# Break.net
KiCad netlist of a schematic drawn in EAGLE
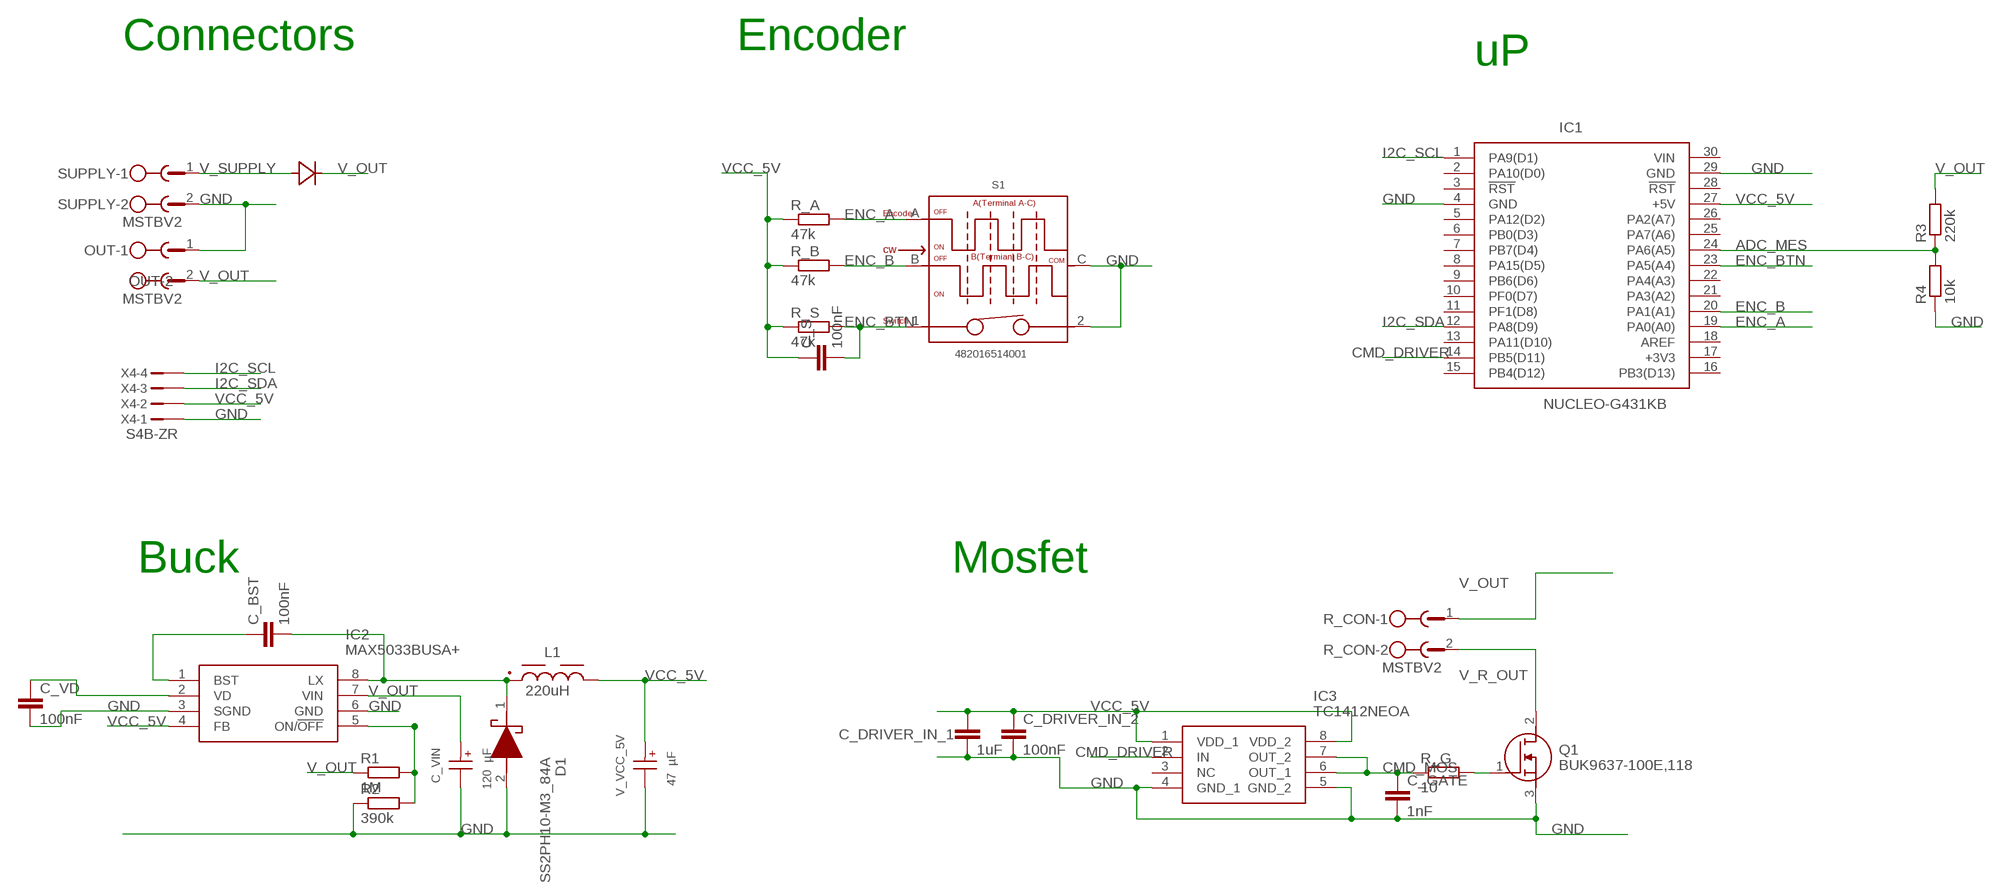
[diagram p0: schematic, sheet 1]

(export (version "E")
  (design (tool "Eeschema 10.0.6"))
  (components
    (comp (ref "C_BST")
      (value "100nF")
      (footprint "eagle-import:C0603")
      (libsource (lib "eagle-import") (part "C-EUC0603"))
    )
    (comp (ref "C_DRIVER_IN_1")
      (value "1uF")
      (footprint "eagle-import:C0603")
      (libsource (lib "eagle-import") (part "C-EUC0603"))
    )
    (comp (ref "C_DRIVER_IN_2")
      (value "100nF")
      (footprint "eagle-import:C0603")
      (libsource (lib "eagle-import") (part "C-EUC0603"))
    )
    (comp (ref "C_GATE")
      (value "1nF")
      (footprint "eagle-import:C0603")
      (libsource (lib "eagle-import") (part "C-EUC0603"))
    )
    (comp (ref "C_S")
      (value "100nF")
      (footprint "eagle-import:C0603")
      (libsource (lib "eagle-import") (part "C-EUC0603"))
    )
    (comp (ref "C_VD")
      (value "100nF")
      (footprint "eagle-import:C0603")
      (libsource (lib "eagle-import") (part "C-EUC0603"))
    )
    (comp (ref "C_VIN")
      (value "120 µF")
      (footprint "eagle-import:WCAP-ATG8_18X41X7.5(DXL)")
      (libsource (lib "eagle-import") (part "WCAP-ATG8_18X41_860011381013"))
    )
    (comp (ref "D1")
      (value "SS2PH10-M3_84A")
      (footprint "eagle-import:DO-220AA")
      (fields
        (field (name "MANUFACTURER_PART_NUMBER") "SS2PH10-M3/84A")
        (field (name "MOUSER_PART_NUMBER") "625-SS2PH10-M3")
      )
      (libsource (lib "eagle-import") (part "SS2PH10-M3_84A"))
    )
    (comp (ref "IC1")
      (value "NUCLEO-G431KB")
      (footprint "eagle-import:DIPS1524W66P254L5029H1500Q30N")
      (fields (field (name "ARROW_PART_NUMBER") "NUCLEO-F303K8") (field (name "RS_PART_NUMBER") "9092862"))
      (libsource (lib "eagle-import") (part "NUCLEO-G431KB"))
    )
    (comp (ref "IC2")
      (value "MAX5033BUSA+")
      (footprint "eagle-import:SOIC127P600X175-8N")
      (fields (field (name "MOUSER_PART_NUMBER") "700-MAX5033BUSA"))
      (libsource (lib "eagle-import") (part "MAX5033BUSA+"))
    )
    (comp (ref "IC3")
      (value "TC1412NEOA")
      (footprint "eagle-import:SOIC127P600X175-8N")
      (fields (field (name "MOUSER_PART_NUMBER") "579-TC1412NEOA"))
      (libsource (lib "eagle-import") (part "TC1412NEOA"))
    )
    (comp (ref "L1")
      (value "220uH")
      (footprint "eagle-import:WE-PDA_1260")
      (libsource (lib "eagle-import") (part "WE-PDA_1260_784771221"))
    )
    (comp (ref "OUT")
      (value "MSTBV2")
      (footprint "eagle-import:MSTBV2")
      (fields (field (name "MPN") "MSTBV 2,5/2-GF-5.08"))
      (libsource (lib "eagle-import") (part "MSTBV2"))
    )
    (comp (ref "Q1")
      (value "BUK9637-100E,118")
      (footprint "eagle-import:PSMN4R480BS118")
      (fields (field (name "MOUSER_PART_NUMBER") "771-BUK9637-100E118"))
      (libsource (lib "eagle-import") (part "BUK9637-100E,118"))
    )
    (comp (ref "R1")
      (value "1M")
      (footprint "eagle-import:R0603")
      (libsource (lib "eagle-import") (part "R-EU_R0603"))
    )
    (comp (ref "R2")
      (value "390k")
      (footprint "eagle-import:R0603")
      (libsource (lib "eagle-import") (part "R-EU_R0603"))
    )
    (comp (ref "R3")
      (value "220k")
      (footprint "eagle-import:R0603")
      (libsource (lib "eagle-import") (part "R-EU_R0603"))
    )
    (comp (ref "R4")
      (value "10k")
      (footprint "eagle-import:R0603")
      (libsource (lib "eagle-import") (part "R-EU_R0603"))
    )
    (comp (ref "R_A")
      (value "47k")
      (footprint "eagle-import:R0603")
      (libsource (lib "eagle-import") (part "R-EU_R0603"))
    )
    (comp (ref "R_B")
      (value "47k")
      (footprint "eagle-import:R0603")
      (libsource (lib "eagle-import") (part "R-EU_R0603"))
    )
    (comp (ref "R_CON")
      (value "MSTBV2")
      (footprint "eagle-import:MSTBV2")
      (fields (field (name "MPN") "MSTBV 2,5/2-GF-5.08"))
      (libsource (lib "eagle-import") (part "MSTBV2"))
    )
    (comp (ref "R_G")
      (value "10")
      (footprint "eagle-import:R1206")
      (libsource (lib "eagle-import") (part "R-EU_R1206"))
    )
    (comp (ref "R_S")
      (value "47k")
      (footprint "eagle-import:R0603")
      (libsource (lib "eagle-import") (part "R-EU_R0603"))
    )
    (comp (ref "S1")
      (value "482016514001")
      (footprint "eagle-import:WS-ENTV_4820XX514001")
      (libsource (lib "eagle-import") (part "482016514001"))
    )
    (comp (ref "SUPPLY")
      (value "MSTBV2")
      (footprint "eagle-import:MSTBV2")
      (fields (field (name "MPN") "MSTBV 2,5/2-GF-5.08"))
      (libsource (lib "eagle-import") (part "MSTBV2"))
    )
    (comp (ref "U$1")
      (value "VS-15TG060S-M3")
      (footprint "eagle-import:SMD-220")
      (libsource (lib "eagle-import") (part "VS-15TG060S-M3"))
    )
    (comp (ref "V_VCC_5V")
      (value "47 µF")
      (footprint "eagle-import:WCAP-ASLL_6.3X5.5(DXL)")
      (libsource (lib "eagle-import") (part "WCAP-ASLL_6.3X5.5_865060443004"))
    )
    (comp (ref "X4")
      (value "S4B-ZR")
      (footprint "eagle-import:S4B-ZR")
      (fields (field (name "MF") "FARNELL") (field (name "MPN") "S4B-ZR(LF)(SN)"))
      (libsource (lib "eagle-import") (part "?4B-ZRS"))
    )
  )
  (nets
    (net (code "1") (name "/ADC_MES") (class "Default")
      (node (ref "IC1") (pin "24") (pinfunction "PA6(A5)_24") (pintype "bidirectional"))
      (node (ref "R3") (pin "1") (pinfunction "1_1") (pintype "passive"))
      (node (ref "R4") (pin "2") (pinfunction "2_2") (pintype "passive"))
    )
    (net (code "2") (name "/CMD_DRIVER") (class "Default")
      (node (ref "IC1") (pin "14") (pinfunction "PB5(D11)_14") (pintype "bidirectional"))
      (node (ref "IC3") (pin "2") (pinfunction "IN_2") (pintype "bidirectional"))
    )
    (net (code "3") (name "/CMD_MOS") (class "Default")
      (node (ref "C_GATE") (pin "1") (pinfunction "1_1") (pintype "passive"))
      (node (ref "IC3") (pin "6") (pinfunction "OUT_1_6") (pintype "bidirectional"))
      (node (ref "IC3") (pin "7") (pinfunction "OUT_2_7") (pintype "bidirectional"))
      (node (ref "R_G") (pin "1") (pinfunction "1_1") (pintype "passive"))
    )
    (net (code "4") (name "/ENC_A") (class "Default")
      (node (ref "IC1") (pin "19") (pinfunction "PA0(A0)_19") (pintype "bidirectional"))
      (node (ref "R_A") (pin "2") (pinfunction "2_2") (pintype "passive"))
      (node (ref "S1") (pin "A") (pinfunction "A_A") (pintype "passive"))
    )
    (net (code "5") (name "/ENC_B") (class "Default")
      (node (ref "IC1") (pin "20") (pinfunction "PA1(A1)_20") (pintype "bidirectional"))
      (node (ref "R_B") (pin "2") (pinfunction "2_2") (pintype "passive"))
      (node (ref "S1") (pin "B") (pinfunction "B_B") (pintype "passive"))
    )
    (net (code "6") (name "/ENC_BTN") (class "Default")
      (node (ref "C_S") (pin "2") (pinfunction "2_2") (pintype "passive"))
      (node (ref "IC1") (pin "23") (pinfunction "PA5(A4)_23") (pintype "bidirectional"))
      (node (ref "R_S") (pin "2") (pinfunction "2_2") (pintype "passive"))
      (node (ref "S1") (pin "1") (pinfunction "1_1") (pintype "passive"))
    )
    (net (code "7") (name "/GND") (class "Default")
      (node (ref "C_DRIVER_IN_1") (pin "2") (pinfunction "2_2") (pintype "passive"))
      (node (ref "C_DRIVER_IN_2") (pin "2") (pinfunction "2_2") (pintype "passive"))
      (node (ref "C_GATE") (pin "2") (pinfunction "2_2") (pintype "passive"))
      (node (ref "C_VD") (pin "2") (pinfunction "2_2") (pintype "passive"))
      (node (ref "C_VIN") (pin "2") (pinfunction "-_2") (pintype "passive"))
      (node (ref "D1") (pin "2") (pinfunction "A_2") (pintype "bidirectional"))
      (node (ref "IC1") (pin "29") (pinfunction "GND_29") (pintype "passive"))
      (node (ref "IC1") (pin "4") (pinfunction "GND_4") (pintype "passive"))
      (node (ref "IC2") (pin "3") (pinfunction "SGND_3") (pintype "bidirectional"))
      (node (ref "IC2") (pin "6") (pinfunction "GND_6") (pintype "bidirectional"))
      (node (ref "IC3") (pin "4") (pinfunction "GND_1_4") (pintype "bidirectional"))
      (node (ref "IC3") (pin "5") (pinfunction "GND_2_5") (pintype "bidirectional"))
      (node (ref "OUT") (pin "1") (pinfunction "1_1") (pintype "passive"))
      (node (ref "Q1") (pin "3") (pinfunction "S_3") (pintype "bidirectional"))
      (node (ref "R2") (pin "1") (pinfunction "1_1") (pintype "passive"))
      (node (ref "R4") (pin "1") (pinfunction "1_1") (pintype "passive"))
      (node (ref "S1") (pin "2") (pinfunction "2_2") (pintype "passive"))
      (node (ref "S1") (pin "C") (pinfunction "COM_C") (pintype "passive"))
      (node (ref "SUPPLY") (pin "2") (pinfunction "1_2") (pintype "passive"))
      (node (ref "V_VCC_5V") (pin "2") (pinfunction "-_2") (pintype "passive"))
      (node (ref "X4") (pin "1") (pinfunction "1_1") (pintype "passive"))
    )
    (net (code "8") (name "/I2C_SCL") (class "Default")
      (node (ref "IC1") (pin "1") (pinfunction "PA9(D1)_1") (pintype "bidirectional"))
      (node (ref "X4") (pin "4") (pinfunction "1_4") (pintype "passive"))
    )
    (net (code "9") (name "/I2C_SDA") (class "Default")
      (node (ref "IC1") (pin "12") (pinfunction "PA8(D9)_12") (pintype "bidirectional"))
      (node (ref "X4") (pin "3") (pinfunction "1_3") (pintype "passive"))
    )
    (net (code "10") (name "/VCC_5V") (class "Default")
      (node (ref "C_DRIVER_IN_1") (pin "1") (pinfunction "1_1") (pintype "passive"))
      (node (ref "C_DRIVER_IN_2") (pin "1") (pinfunction "1_1") (pintype "passive"))
      (node (ref "C_S") (pin "1") (pinfunction "1_1") (pintype "passive"))
      (node (ref "IC1") (pin "27") (pinfunction "+5V_27") (pintype "passive"))
      (node (ref "IC2") (pin "4") (pinfunction "FB_4") (pintype "bidirectional"))
      (node (ref "IC3") (pin "1") (pinfunction "VDD_1_1") (pintype "bidirectional"))
      (node (ref "IC3") (pin "8") (pinfunction "VDD_2_8") (pintype "bidirectional"))
      (node (ref "L1") (pin "2") (pinfunction "2_2") (pintype "passive"))
      (node (ref "R_A") (pin "1") (pinfunction "1_1") (pintype "passive"))
      (node (ref "R_B") (pin "1") (pinfunction "1_1") (pintype "passive"))
      (node (ref "R_S") (pin "1") (pinfunction "1_1") (pintype "passive"))
      (node (ref "V_VCC_5V") (pin "1") (pinfunction "+_1") (pintype "passive"))
      (node (ref "X4") (pin "2") (pinfunction "1_2") (pintype "passive"))
    )
    (net (code "11") (name "/V_OUT") (class "Default")
      (node (ref "C_VIN") (pin "1") (pinfunction "+_1") (pintype "passive"))
      (node (ref "IC2") (pin "7") (pinfunction "VIN_7") (pintype "bidirectional"))
      (node (ref "OUT") (pin "2") (pinfunction "1_2") (pintype "passive"))
      (node (ref "R1") (pin "1") (pinfunction "1_1") (pintype "passive"))
      (node (ref "R3") (pin "2") (pinfunction "2_2") (pintype "passive"))
      (node (ref "R_CON") (pin "1") (pinfunction "1_1") (pintype "passive"))
      (node (ref "U$1") (pin "P$4") (pinfunction "C_P$4") (pintype "passive"))
    )
    (net (code "12") (name "/V_R_OUT") (class "Default")
      (node (ref "Q1") (pin "2") (pinfunction "D_2") (pintype "bidirectional"))
      (node (ref "R_CON") (pin "2") (pinfunction "1_2") (pintype "passive"))
    )
    (net (code "13") (name "/V_SUPPLY") (class "Default")
      (node (ref "SUPPLY") (pin "1") (pinfunction "1_1") (pintype "passive"))
      (node (ref "U$1") (pin "P$3") (pinfunction "A_P$3") (pintype "passive"))
    )
    (net (code "14") (name "Net-(D1-K)") (class "Default")
      (node (ref "C_BST") (pin "2") (pinfunction "2_2") (pintype "passive"))
      (node (ref "D1") (pin "1") (pinfunction "K_1") (pintype "bidirectional"))
      (node (ref "IC2") (pin "8") (pinfunction "LX_8") (pintype "bidirectional"))
      (node (ref "L1") (pin "1") (pinfunction "1_1") (pintype "passive"))
    )
    (net (code "15") (name "Net-(IC2-BST)") (class "Default")
      (node (ref "C_BST") (pin "1") (pinfunction "1_1") (pintype "passive"))
      (node (ref "IC2") (pin "1") (pinfunction "BST_1") (pintype "bidirectional"))
    )
    (net (code "16") (name "Net-(IC2-ON{slash}~{OFF})") (class "Default")
      (node (ref "IC2") (pin "5") (pinfunction "ON/~{OFF}_5") (pintype "bidirectional"))
      (node (ref "R1") (pin "2") (pinfunction "2_2") (pintype "passive"))
      (node (ref "R2") (pin "2") (pinfunction "2_2") (pintype "passive"))
    )
    (net (code "17") (name "Net-(IC2-VD)") (class "Default")
      (node (ref "C_VD") (pin "1") (pinfunction "1_1") (pintype "passive"))
      (node (ref "IC2") (pin "2") (pinfunction "VD_2") (pintype "bidirectional"))
    )
    (net (code "18") (name "Net-(Q1-G)") (class "Default")
      (node (ref "Q1") (pin "1") (pinfunction "G_1") (pintype "bidirectional"))
      (node (ref "R_G") (pin "2") (pinfunction "2_2") (pintype "passive"))
    )
    (net (code "19") (name "unconnected-(IC1-+3V3-Pad17)") (class "Default")
      (node (ref "IC1") (pin "17") (pinfunction "+3V3_17") (pintype "passive"))
    )
    (net (code "20") (name "unconnected-(IC1-AREF-Pad18)") (class "Default")
      (node (ref "IC1") (pin "18") (pinfunction "AREF_18") (pintype "passive"))
    )
    (net (code "21") (name "unconnected-(IC1-PA2(A7)-Pad26)") (class "Default")
      (node (ref "IC1") (pin "26") (pinfunction "PA2(A7)_26") (pintype "bidirectional"))
    )
    (net (code "22") (name "unconnected-(IC1-PA3(A2)-Pad21)") (class "Default")
      (node (ref "IC1") (pin "21") (pinfunction "PA3(A2)_21") (pintype "bidirectional"))
    )
    (net (code "23") (name "unconnected-(IC1-PA4(A3)-Pad22)") (class "Default")
      (node (ref "IC1") (pin "22") (pinfunction "PA4(A3)_22") (pintype "bidirectional"))
    )
    (net (code "24") (name "unconnected-(IC1-PA7(A6)-Pad25)") (class "Default")
      (node (ref "IC1") (pin "25") (pinfunction "PA7(A6)_25") (pintype "bidirectional"))
    )
    (net (code "25") (name "unconnected-(IC1-PA10(D0)-Pad2)") (class "Default")
      (node (ref "IC1") (pin "2") (pinfunction "PA10(D0)_2") (pintype "bidirectional"))
    )
    (net (code "26") (name "unconnected-(IC1-PA11(D10)-Pad13)") (class "Default")
      (node (ref "IC1") (pin "13") (pinfunction "PA11(D10)_13") (pintype "bidirectional"))
    )
    (net (code "27") (name "unconnected-(IC1-PA12(D2)-Pad5)") (class "Default")
      (node (ref "IC1") (pin "5") (pinfunction "PA12(D2)_5") (pintype "bidirectional"))
    )
    (net (code "28") (name "unconnected-(IC1-PA15(D5)-Pad8)") (class "Default")
      (node (ref "IC1") (pin "8") (pinfunction "PA15(D5)_8") (pintype "bidirectional"))
    )
    (net (code "29") (name "unconnected-(IC1-PB0(D3)-Pad6)") (class "Default")
      (node (ref "IC1") (pin "6") (pinfunction "PB0(D3)_6") (pintype "bidirectional"))
    )
    (net (code "30") (name "unconnected-(IC1-PB3(D13)-Pad16)") (class "Default")
      (node (ref "IC1") (pin "16") (pinfunction "PB3(D13)_16") (pintype "bidirectional"))
    )
    (net (code "31") (name "unconnected-(IC1-PB4(D12)-Pad15)") (class "Default")
      (node (ref "IC1") (pin "15") (pinfunction "PB4(D12)_15") (pintype "bidirectional"))
    )
    (net (code "32") (name "unconnected-(IC1-PB6(D6)-Pad9)") (class "Default")
      (node (ref "IC1") (pin "9") (pinfunction "PB6(D6)_9") (pintype "bidirectional"))
    )
    (net (code "33") (name "unconnected-(IC1-PB7(D4)-Pad7)") (class "Default")
      (node (ref "IC1") (pin "7") (pinfunction "PB7(D4)_7") (pintype "bidirectional"))
    )
    (net (code "34") (name "unconnected-(IC1-PF0(D7)-Pad10)") (class "Default")
      (node (ref "IC1") (pin "10") (pinfunction "PF0(D7)_10") (pintype "bidirectional"))
    )
    (net (code "35") (name "unconnected-(IC1-PF1(D8)-Pad11)") (class "Default")
      (node (ref "IC1") (pin "11") (pinfunction "PF1(D8)_11") (pintype "bidirectional"))
    )
    (net (code "36") (name "unconnected-(IC1-VIN-Pad30)") (class "Default")
      (node (ref "IC1") (pin "30") (pinfunction "VIN_30") (pintype "passive"))
    )
    (net (code "37") (name "unconnected-(IC1-~{RST}-Pad3)") (class "Default")
      (node (ref "IC1") (pin "3") (pinfunction "~{RST}_3") (pintype "bidirectional"))
    )
    (net (code "38") (name "unconnected-(IC1-~{RST}-Pad28)") (class "Default")
      (node (ref "IC1") (pin "28") (pinfunction "~{RST}_28") (pintype "bidirectional"))
    )
    (net (code "39") (name "unconnected-(IC3-NC-Pad3)") (class "Default")
      (node (ref "IC3") (pin "3") (pinfunction "NC_3") (pintype "no_connect"))
    )
  )
)
